# 23_PCIE_2_0_x1Lane_RC_B_Key.net
KiCad netlist of a schematic drawn in Altium Designer
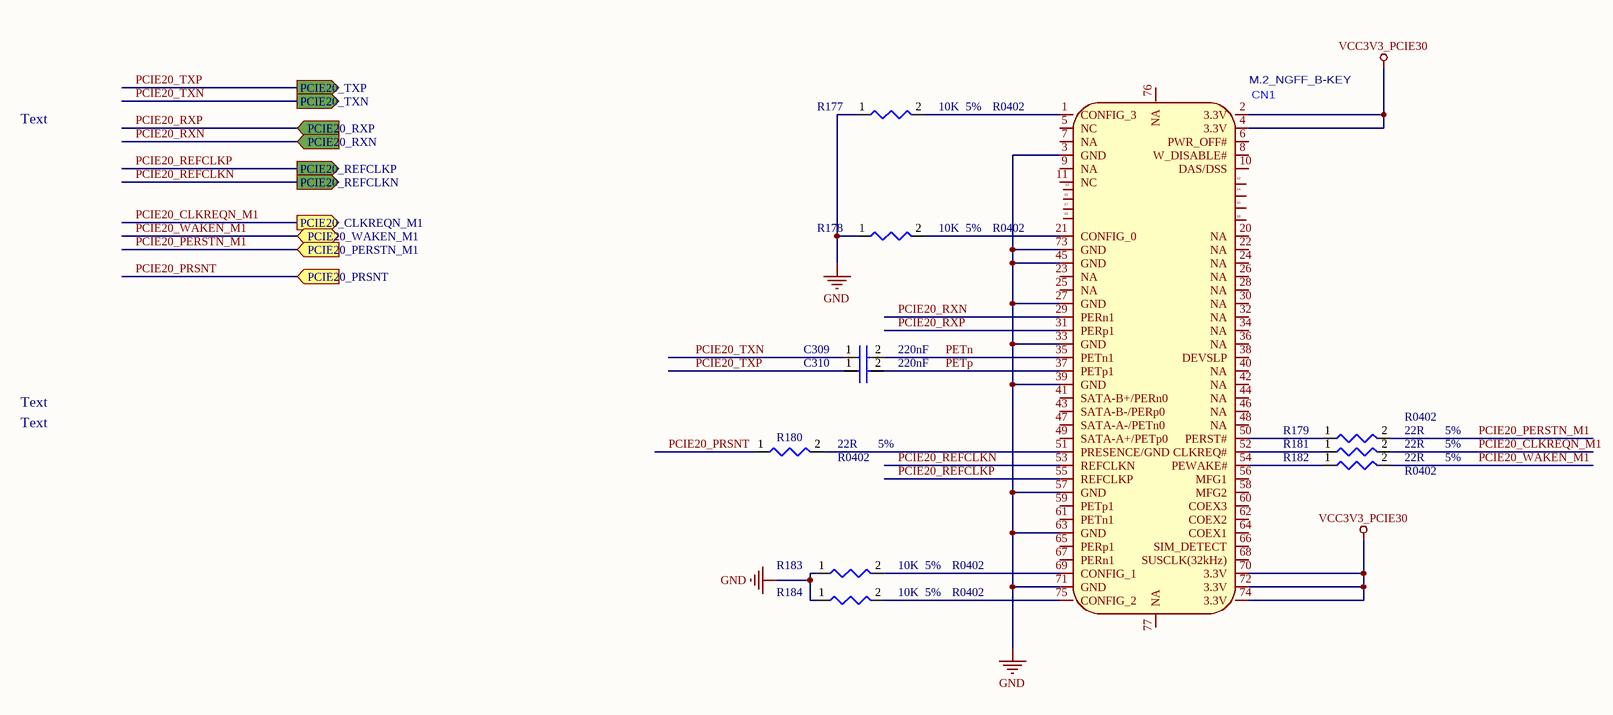
[diagram p0: 23_PCIE 2.0 x1Lane RC_B_Key .SchDoc]

(export (version "E")
  (design (tool "Eeschema 10.0.6"))
  (components
    (comp (ref "C309")
      (value "220nF")
      (footprint "C0201")
      (description "cap,220.00nF,+/-10%,10V,X5R,C0201")
      (fields
        (field (name "MANUFACTURER") "TDK")
        (field (name "TOLERANCE") "10%")
        (field (name "CREATED BY") "JJJ")
      )
      (libsource (lib "*") (part "CAP NP"))
    )
    (comp (ref "C310")
      (value "220nF")
      (footprint "C0201")
      (description "cap,220.00nF,+/-10%,10V,X5R,C0201")
      (fields
        (field (name "MANUFACTURER") "TDK")
        (field (name "TOLERANCE") "10%")
        (field (name "CREATED BY") "JJJ")
      )
      (libsource (lib "*") (part "CAP NP"))
    )
    (comp (ref "CN1")
      (value "M.2_NGFF_B-KEY")
      (footprint "PCIE-SMD_TE_2199230-4")
      (libsource (lib "RK3568核心板") (part "M.2_NGFF_B-KEY"))
    )
    (comp (ref "R177")
      (value "10K")
      (footprint "R0402")
      (description "通用厚膜电阻,10K,+/-5%,R0402,1/16W.")
      (fields
        (field (name "PCB FOOTPRINT") "R0402")
        (field (name "TOLERANCE") "5%")
        (field (name "MANUFACTURER") "YAGEO")
        (field (name "CREATED BY") "YTL")
      )
      (libsource (lib "*") (part "RESISTOR_Dup1"))
    )
    (comp (ref "R178")
      (value "10K")
      (footprint "R0402")
      (description "通用厚膜电阻,10K,+/-5%,R0402,1/16W.")
      (fields
        (field (name "PCB FOOTPRINT") "R0402")
        (field (name "TOLERANCE") "5%")
        (field (name "MANUFACTURER") "YAGEO")
        (field (name "CREATED BY") "YTL")
      )
      (libsource (lib "*") (part "RESISTOR_Dup1"))
    )
    (comp (ref "R179")
      (value "22R")
      (footprint "R0402")
      (description "通用厚膜电阻,22R,+/-5%,R0402,1/16W.")
      (fields
        (field (name "PCB FOOTPRINT") "R0402")
        (field (name "TOLERANCE") "5%")
        (field (name "MANUFACTURER") "YAGEO")
        (field (name "CREATED BY") "YTL")
      )
      (libsource (lib "*") (part "RESISTOR_Dup1"))
    )
    (comp (ref "R180")
      (value "22R")
      (footprint "R0402")
      (description "通用厚膜电阻,22R,+/-5%,R0402,1/16W.")
      (fields
        (field (name "PCB FOOTPRINT") "R0402")
        (field (name "TOLERANCE") "5%")
        (field (name "MANUFACTURER") "YAGEO")
        (field (name "CREATED BY") "YTL")
      )
      (libsource (lib "*") (part "RESISTOR_Dup1"))
    )
    (comp (ref "R181")
      (value "22R")
      (footprint "R0402")
      (description "通用厚膜电阻,22R,+/-5%,R0402,1/16W.")
      (fields
        (field (name "TOLERANCE") "5%")
        (field (name "MANUFACTURER") "YAGEO")
        (field (name "CREATED BY") "YTL")
      )
      (libsource (lib "*") (part "RESISTOR_Dup1"))
    )
    (comp (ref "R182")
      (value "22R")
      (footprint "R0402")
      (description "通用厚膜电阻,22R,+/-5%,R0402,1/16W.")
      (fields
        (field (name "PCB FOOTPRINT") "R0402")
        (field (name "TOLERANCE") "5%")
        (field (name "MANUFACTURER") "YAGEO")
        (field (name "CREATED BY") "YTL")
      )
      (libsource (lib "*") (part "RESISTOR_Dup1"))
    )
    (comp (ref "R183")
      (value "10K")
      (footprint "R0402")
      (description "通用厚膜电阻,10K,+/-5%,R0402,1/16W.")
      (fields
        (field (name "PCB FOOTPRINT") "R0402")
        (field (name "TOLERANCE") "5%")
        (field (name "MANUFACTURER") "YAGEO")
        (field (name "CREATED BY") "YTL")
      )
      (libsource (lib "*") (part "RESISTOR_Dup1"))
    )
    (comp (ref "R184")
      (value "10K")
      (footprint "R0402")
      (description "通用厚膜电阻,10K,+/-5%,R0402,1/16W.")
      (fields
        (field (name "PCB FOOTPRINT") "R0402")
        (field (name "TOLERANCE") "5%")
        (field (name "MANUFACTURER") "YAGEO")
        (field (name "CREATED BY") "YTL")
      )
      (libsource (lib "*") (part "RESISTOR_Dup1"))
    )
  )
  (nets
    (net (code "1") (name "/PCIE20_CLKREQN_M1") (class "Default")
      (node (ref "R181") (pin "2") (pinfunction "2_2") (pintype "passive"))
    )
    (net (code "2") (name "/PCIE20_PERSTN_M1") (class "Default")
      (node (ref "R179") (pin "2") (pinfunction "2_2") (pintype "passive"))
    )
    (net (code "3") (name "/PCIE20_PRSNT") (class "Default")
      (node (ref "R180") (pin "1") (pinfunction "1_1") (pintype "passive"))
    )
    (net (code "4") (name "/PCIE20_REFCLKN") (class "Default")
      (node (ref "CN1") (pin "53") (pinfunction "REFCLKN_53") (pintype "passive"))
    )
    (net (code "5") (name "/PCIE20_REFCLKP") (class "Default")
      (node (ref "CN1") (pin "55") (pinfunction "REFCLKP_55") (pintype "passive"))
    )
    (net (code "6") (name "/PCIE20_RXN") (class "Default")
      (node (ref "CN1") (pin "29") (pinfunction "PERn1_29") (pintype "passive"))
    )
    (net (code "7") (name "/PCIE20_RXP") (class "Default")
      (node (ref "CN1") (pin "31") (pinfunction "PERp1_31") (pintype "passive"))
    )
    (net (code "8") (name "/PCIE20_TXN") (class "Default")
      (node (ref "C309") (pin "1") (pinfunction "1_1") (pintype "passive"))
    )
    (net (code "9") (name "/PCIE20_TXP") (class "Default")
      (node (ref "C310") (pin "1") (pinfunction "1_1") (pintype "passive"))
    )
    (net (code "10") (name "/PCIE20_WAKEN_M1") (class "Default")
      (node (ref "R182") (pin "2") (pinfunction "2_2") (pintype "passive"))
    )
    (net (code "11") (name "/PETn") (class "Default")
      (node (ref "C309") (pin "2") (pinfunction "2_2") (pintype "passive"))
      (node (ref "CN1") (pin "35") (pinfunction "PETn1_35") (pintype "passive"))
    )
    (net (code "12") (name "/PETp") (class "Default")
      (node (ref "C310") (pin "2") (pinfunction "2_2") (pintype "passive"))
      (node (ref "CN1") (pin "37") (pinfunction "PETp1_37") (pintype "passive"))
    )
    (net (code "13") (name "GND") (class "Default")
      (node (ref "CN1") (pin "27") (pinfunction "GND_27") (pintype "passive"))
      (node (ref "CN1") (pin "3") (pinfunction "GND_3") (pintype "passive"))
      (node (ref "CN1") (pin "33") (pinfunction "GND_33") (pintype "passive"))
      (node (ref "CN1") (pin "39") (pinfunction "GND_39") (pintype "passive"))
      (node (ref "CN1") (pin "45") (pinfunction "GND_45") (pintype "passive"))
      (node (ref "CN1") (pin "57") (pinfunction "GND_57") (pintype "passive"))
      (node (ref "CN1") (pin "63") (pinfunction "GND_63") (pintype "passive"))
      (node (ref "CN1") (pin "71") (pinfunction "GND_71") (pintype "passive"))
      (node (ref "CN1") (pin "73") (pinfunction "GND_73") (pintype "passive"))
      (node (ref "R177") (pin "1") (pinfunction "1_1") (pintype "passive"))
      (node (ref "R178") (pin "1") (pinfunction "1_1") (pintype "passive"))
      (node (ref "R183") (pin "1") (pinfunction "1_1") (pintype "passive"))
      (node (ref "R184") (pin "1") (pinfunction "1_1") (pintype "passive"))
    )
    (net (code "14") (name "Net-(CN1-CLKREQ#)") (class "Default")
      (node (ref "CN1") (pin "52") (pinfunction "CLKREQ#_52") (pintype "passive"))
      (node (ref "R181") (pin "1") (pinfunction "1_1") (pintype "passive"))
    )
    (net (code "15") (name "Net-(CN1-CONFIG_0)") (class "Default")
      (node (ref "CN1") (pin "21") (pinfunction "CONFIG_0_21") (pintype "passive"))
      (node (ref "R178") (pin "2") (pinfunction "2_2") (pintype "passive"))
    )
    (net (code "16") (name "Net-(CN1-CONFIG_1)") (class "Default")
      (node (ref "CN1") (pin "69") (pinfunction "CONFIG_1_69") (pintype "passive"))
      (node (ref "R183") (pin "2") (pinfunction "2_2") (pintype "passive"))
    )
    (net (code "17") (name "Net-(CN1-CONFIG_2)") (class "Default")
      (node (ref "CN1") (pin "75") (pinfunction "CONFIG_2_75") (pintype "passive"))
      (node (ref "R184") (pin "2") (pinfunction "2_2") (pintype "passive"))
    )
    (net (code "18") (name "Net-(CN1-CONFIG_3)") (class "Default")
      (node (ref "CN1") (pin "1") (pinfunction "CONFIG_3_1") (pintype "passive"))
      (node (ref "R177") (pin "2") (pinfunction "2_2") (pintype "passive"))
    )
    (net (code "19") (name "Net-(CN1-PERST#)") (class "Default")
      (node (ref "CN1") (pin "50") (pinfunction "PERST#_50") (pintype "passive"))
      (node (ref "R179") (pin "1") (pinfunction "1_1") (pintype "passive"))
    )
    (net (code "20") (name "Net-(CN1-PEWAKE#)") (class "Default")
      (node (ref "CN1") (pin "54") (pinfunction "PEWAKE#_54") (pintype "passive"))
      (node (ref "R182") (pin "1") (pinfunction "1_1") (pintype "passive"))
    )
    (net (code "21") (name "Net-(CN1-PRESENCE{slash}GND)") (class "Default")
      (node (ref "CN1") (pin "51") (pinfunction "PRESENCE/GND_51") (pintype "passive"))
      (node (ref "R180") (pin "2") (pinfunction "2_2") (pintype "passive"))
    )
    (net (code "22") (name "VCC3V3_PCIE30") (class "Default")
      (node (ref "CN1") (pin "2") (pinfunction "3.3V_2") (pintype "passive"))
      (node (ref "CN1") (pin "4") (pinfunction "3.3V_4") (pintype "passive"))
      (node (ref "CN1") (pin "70") (pinfunction "3.3V_70") (pintype "passive"))
      (node (ref "CN1") (pin "72") (pinfunction "3.3V_72") (pintype "passive"))
      (node (ref "CN1") (pin "74") (pinfunction "3.3V_74") (pintype "passive"))
    )
    (net (code "23") (name "unconnected-(CN1-COEX1-Pad64)") (class "Default")
      (node (ref "CN1") (pin "64") (pinfunction "COEX1_64") (pintype "passive"))
    )
    (net (code "24") (name "unconnected-(CN1-COEX2-Pad62)") (class "Default")
      (node (ref "CN1") (pin "62") (pinfunction "COEX2_62") (pintype "passive"))
    )
    (net (code "25") (name "unconnected-(CN1-COEX3-Pad60)") (class "Default")
      (node (ref "CN1") (pin "60") (pinfunction "COEX3_60") (pintype "passive"))
    )
    (net (code "26") (name "unconnected-(CN1-DAS{slash}DSS-Pad10)") (class "Default")
      (node (ref "CN1") (pin "10") (pinfunction "DAS/DSS_10") (pintype "passive"))
    )
    (net (code "27") (name "unconnected-(CN1-DEVSLP-Pad38)") (class "Default")
      (node (ref "CN1") (pin "38") (pinfunction "DEVSLP_38") (pintype "passive"))
    )
    (net (code "28") (name "unconnected-(CN1-MFG1-Pad56)") (class "Default")
      (node (ref "CN1") (pin "56") (pinfunction "MFG1_56") (pintype "passive"))
    )
    (net (code "29") (name "unconnected-(CN1-MFG2-Pad58)") (class "Default")
      (node (ref "CN1") (pin "58") (pinfunction "MFG2_58") (pintype "passive"))
    )
    (net (code "30") (name "unconnected-(CN1-NA-Pad7)") (class "Default")
      (node (ref "CN1") (pin "7") (pinfunction "NA_7") (pintype "passive"))
    )
    (net (code "31") (name "unconnected-(CN1-NA-Pad9)") (class "Default")
      (node (ref "CN1") (pin "9") (pinfunction "NA_9") (pintype "passive"))
    )
    (net (code "32") (name "unconnected-(CN1-NA-Pad20)") (class "Default")
      (node (ref "CN1") (pin "20") (pinfunction "NA_20") (pintype "passive"))
    )
    (net (code "33") (name "unconnected-(CN1-NA-Pad22)") (class "Default")
      (node (ref "CN1") (pin "22") (pinfunction "NA_22") (pintype "passive"))
    )
    (net (code "34") (name "unconnected-(CN1-NA-Pad23)") (class "Default")
      (node (ref "CN1") (pin "23") (pinfunction "NA_23") (pintype "passive"))
    )
    (net (code "35") (name "unconnected-(CN1-NA-Pad24)") (class "Default")
      (node (ref "CN1") (pin "24") (pinfunction "NA_24") (pintype "passive"))
    )
    (net (code "36") (name "unconnected-(CN1-NA-Pad25)") (class "Default")
      (node (ref "CN1") (pin "25") (pinfunction "NA_25") (pintype "passive"))
    )
    (net (code "37") (name "unconnected-(CN1-NA-Pad26)") (class "Default")
      (node (ref "CN1") (pin "26") (pinfunction "NA_26") (pintype "passive"))
    )
    (net (code "38") (name "unconnected-(CN1-NA-Pad28)") (class "Default")
      (node (ref "CN1") (pin "28") (pinfunction "NA_28") (pintype "passive"))
    )
    (net (code "39") (name "unconnected-(CN1-NA-Pad30)") (class "Default")
      (node (ref "CN1") (pin "30") (pinfunction "NA_30") (pintype "passive"))
    )
    (net (code "40") (name "unconnected-(CN1-NA-Pad32)") (class "Default")
      (node (ref "CN1") (pin "32") (pinfunction "NA_32") (pintype "passive"))
    )
    (net (code "41") (name "unconnected-(CN1-NA-Pad34)") (class "Default")
      (node (ref "CN1") (pin "34") (pinfunction "NA_34") (pintype "passive"))
    )
    (net (code "42") (name "unconnected-(CN1-NA-Pad36)") (class "Default")
      (node (ref "CN1") (pin "36") (pinfunction "NA_36") (pintype "passive"))
    )
    (net (code "43") (name "unconnected-(CN1-NA-Pad40)") (class "Default")
      (node (ref "CN1") (pin "40") (pinfunction "NA_40") (pintype "passive"))
    )
    (net (code "44") (name "unconnected-(CN1-NA-Pad42)") (class "Default")
      (node (ref "CN1") (pin "42") (pinfunction "NA_42") (pintype "passive"))
    )
    (net (code "45") (name "unconnected-(CN1-NA-Pad44)") (class "Default")
      (node (ref "CN1") (pin "44") (pinfunction "NA_44") (pintype "passive"))
    )
    (net (code "46") (name "unconnected-(CN1-NA-Pad46)") (class "Default")
      (node (ref "CN1") (pin "46") (pinfunction "NA_46") (pintype "passive"))
    )
    (net (code "47") (name "unconnected-(CN1-NA-Pad48)") (class "Default")
      (node (ref "CN1") (pin "48") (pinfunction "NA_48") (pintype "passive"))
    )
    (net (code "48") (name "unconnected-(CN1-NA-Pad76)") (class "Default")
      (node (ref "CN1") (pin "76") (pinfunction "NA_76") (pintype "passive"))
    )
    (net (code "49") (name "unconnected-(CN1-NA-Pad77)") (class "Default")
      (node (ref "CN1") (pin "77") (pinfunction "NA_77") (pintype "passive"))
    )
    (net (code "50") (name "unconnected-(CN1-NC-Pad5)") (class "Default")
      (node (ref "CN1") (pin "5") (pinfunction "NC_5") (pintype "passive"))
    )
    (net (code "51") (name "unconnected-(CN1-NC-Pad11)") (class "Default")
      (node (ref "CN1") (pin "11") (pinfunction "NC_11") (pintype "passive"))
    )
    (net (code "52") (name "unconnected-(CN1-PERn1-Pad67)") (class "Default")
      (node (ref "CN1") (pin "67") (pinfunction "PERn1_67") (pintype "passive"))
    )
    (net (code "53") (name "unconnected-(CN1-PERp1-Pad65)") (class "Default")
      (node (ref "CN1") (pin "65") (pinfunction "PERp1_65") (pintype "passive"))
    )
    (net (code "54") (name "unconnected-(CN1-PETn1-Pad61)") (class "Default")
      (node (ref "CN1") (pin "61") (pinfunction "PETn1_61") (pintype "passive"))
    )
    (net (code "55") (name "unconnected-(CN1-PETp1-Pad59)") (class "Default")
      (node (ref "CN1") (pin "59") (pinfunction "PETp1_59") (pintype "passive"))
    )
    (net (code "56") (name "unconnected-(CN1-PWR_OFF#-Pad6)") (class "Default")
      (node (ref "CN1") (pin "6") (pinfunction "PWR_OFF#_6") (pintype "passive"))
    )
    (net (code "57") (name "unconnected-(CN1-SATA-A+{slash}PETp0-Pad49)") (class "Default")
      (node (ref "CN1") (pin "49") (pinfunction "SATA-A+/PETp0_49") (pintype "passive"))
    )
    (net (code "58") (name "unconnected-(CN1-SATA-A-{slash}PETn0-Pad47)") (class "Default")
      (node (ref "CN1") (pin "47") (pinfunction "SATA-A-/PETn0_47") (pintype "passive"))
    )
    (net (code "59") (name "unconnected-(CN1-SATA-B+{slash}PERn0-Pad41)") (class "Default")
      (node (ref "CN1") (pin "41") (pinfunction "SATA-B+/PERn0_41") (pintype "passive"))
    )
    (net (code "60") (name "unconnected-(CN1-SATA-B-{slash}PERp0-Pad43)") (class "Default")
      (node (ref "CN1") (pin "43") (pinfunction "SATA-B-/PERp0_43") (pintype "passive"))
    )
    (net (code "61") (name "unconnected-(CN1-SIM_DETECT-Pad66)") (class "Default")
      (node (ref "CN1") (pin "66") (pinfunction "SIM_DETECT_66") (pintype "passive"))
    )
    (net (code "62") (name "unconnected-(CN1-SUSCLK(32kHz)-Pad68)") (class "Default")
      (node (ref "CN1") (pin "68") (pinfunction "SUSCLK(32kHz)_68") (pintype "passive"))
    )
    (net (code "63") (name "unconnected-(CN1-W_DISABLE#-Pad8)") (class "Default")
      (node (ref "CN1") (pin "8") (pinfunction "W_DISABLE#_8") (pintype "passive"))
    )
  )
)
